# Power_Adc.net
KiCad netlist of a schematic drawn in Altium Designer
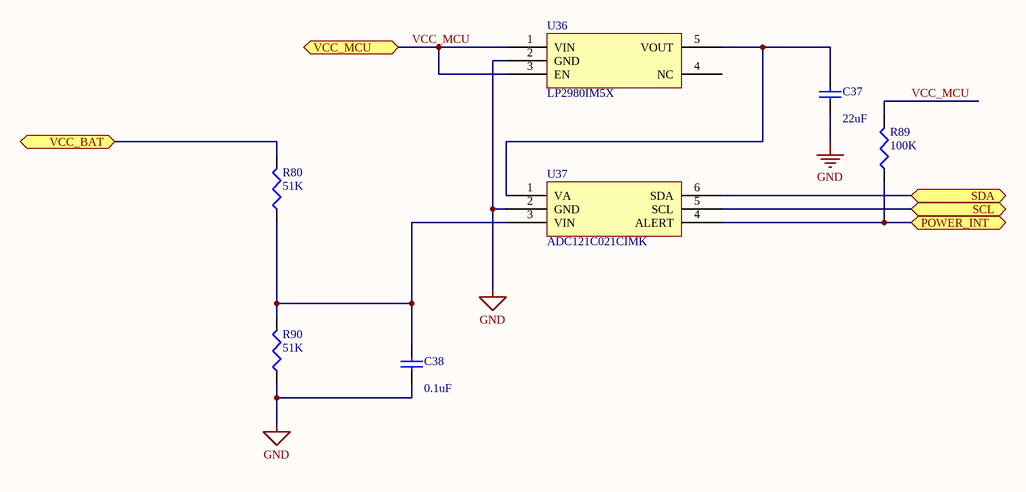
[diagram p0: Power_Adc.SchDoc]

(export (version "E")
  (design (tool "Eeschema 10.0.6"))
  (components
    (comp (ref "C37")
      (value "22uF")
      (footprint "clock:1206")
      (description "Capacitor (Semiconductor SIM Model)")
      (fields (field (name "Comment") "Cap Semi") (field (name "PUBLISHER") "Altium Limited"))
      (libsource (lib "Miscellaneous Devices") (part "Cap Semi"))
    )
    (comp (ref "C38")
      (value "0.1uF")
      (footprint "clock:0603")
      (description "Capacitor (Semiconductor SIM Model)")
      (fields (field (name "Comment") "Cap Semi") (field (name "PUBLISHER") "Altium Limited"))
      (libsource (lib "Miscellaneous Devices") (part "Cap Semi"))
    )
    (comp (ref "R80")
      (value "51K")
      (footprint "clock:0805")
      (description "Resistor")
      (fields (field (name "Comment") "Res3") (field (name "PUBLISHER") "Altium Limited"))
      (libsource (lib "Miscellaneous Devices") (part "Res3"))
    )
    (comp (ref "R89")
      (value "100K")
      (footprint "clock:0603")
      (description "Resistor")
      (fields (field (name "Comment") "Res3") (field (name "PUBLISHER") "Altium Limited"))
      (libsource (lib "Miscellaneous Devices") (part "Res3"))
    )
    (comp (ref "R90")
      (value "51K")
      (footprint "clock:0805")
      (description "Resistor")
      (fields (field (name "Comment") "Res3") (field (name "PUBLISHER") "Altium Limited"))
      (libsource (lib "Miscellaneous Devices") (part "Res3"))
    )
    (comp (ref "U36")
      (value "LP2980IM5X")
      (footprint "clock:DDC-5")
      (libsource (lib "clock") (part "LP2980IM5X"))
    )
    (comp (ref "U37")
      (value "ADC121C021CIMK")
      (footprint "clock:DDC-6")
      (libsource (lib "clock") (part "ADC121C021CIMK"))
    )
  )
  (nets
    (net (code "1") (name "/POWER_INT") (class "Default")
      (node (ref "R89") (pin "1") (pinfunction "1_1") (pintype "passive"))
      (node (ref "U37") (pin "4") (pinfunction "ALERT_4") (pintype "passive"))
    )
    (net (code "2") (name "/SCL") (class "Default")
      (node (ref "U37") (pin "5") (pinfunction "SCL_5") (pintype "passive"))
    )
    (net (code "3") (name "/SDA") (class "Default")
      (node (ref "U37") (pin "6") (pinfunction "SDA_6") (pintype "passive"))
    )
    (net (code "4") (name "/VCC_BAT") (class "Default")
      (node (ref "R80") (pin "2") (pinfunction "2_2") (pintype "passive"))
    )
    (net (code "5") (name "/VCC_MCU") (class "Default")
      (node (ref "R89") (pin "2") (pinfunction "2_2") (pintype "passive"))
      (node (ref "U36") (pin "1") (pinfunction "VIN_1") (pintype "passive"))
      (node (ref "U36") (pin "3") (pinfunction "EN_3") (pintype "passive"))
    )
    (net (code "6") (name "GND") (class "Default")
      (node (ref "C37") (pin "1") (pinfunction "1_1") (pintype "passive"))
      (node (ref "C38") (pin "1") (pinfunction "1_1") (pintype "passive"))
      (node (ref "R90") (pin "1") (pinfunction "1_1") (pintype "passive"))
      (node (ref "U36") (pin "2") (pinfunction "GND_2") (pintype "passive"))
      (node (ref "U37") (pin "2") (pinfunction "GND_2") (pintype "passive"))
    )
    (net (code "7") (name "Net-(U36-VOUT)") (class "Default")
      (node (ref "C37") (pin "2") (pinfunction "2_2") (pintype "passive"))
      (node (ref "U36") (pin "5") (pinfunction "VOUT_5") (pintype "passive"))
      (node (ref "U37") (pin "1") (pinfunction "VA_1") (pintype "passive"))
    )
    (net (code "8") (name "Net-(U37-VIN)") (class "Default")
      (node (ref "C38") (pin "2") (pinfunction "2_2") (pintype "passive"))
      (node (ref "R80") (pin "1") (pinfunction "1_1") (pintype "passive"))
      (node (ref "R90") (pin "2") (pinfunction "2_2") (pintype "passive"))
      (node (ref "U37") (pin "3") (pinfunction "VIN_3") (pintype "passive"))
    )
    (net (code "9") (name "unconnected-(U36-NC-Pad4)") (class "Default")
      (node (ref "U36") (pin "4") (pinfunction "NC_4") (pintype "passive"))
    )
  )
)
